# VNH2SP30.net
KiCad netlist of a schematic drawn in EAGLE
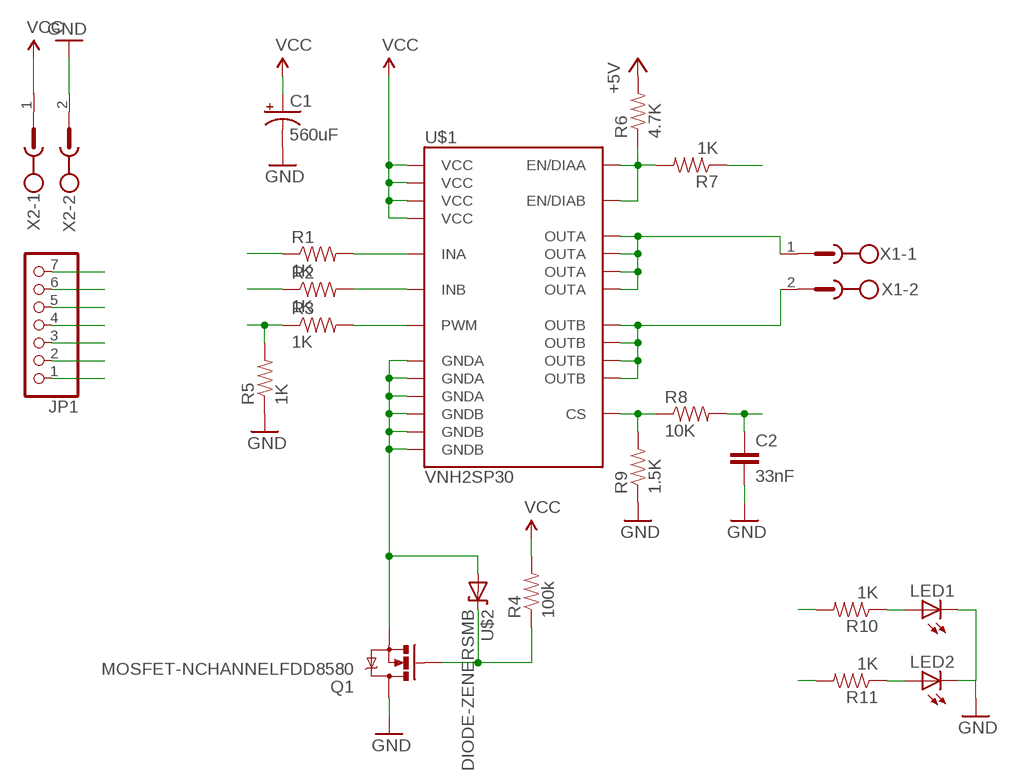
[diagram p0: schematic, sheet 1]

(export (version "E")
  (design (tool "Eeschema 10.0.6"))
  (components
    (comp (ref "C1")
      (value "560uF")
      (footprint "eagle-import:PANASONIC_G")
      (libsource (lib "eagle-import") (part "CAP_POLG"))
    )
    (comp (ref "C2")
      (value "33nF")
      (footprint "eagle-import:1206")
      (libsource (lib "eagle-import") (part "CAP1206"))
    )
    (comp (ref "JP1")
      (value "PINHD-1X7")
      (footprint "eagle-import:1X07")
      (libsource (lib "eagle-import") (part "PINHD-1X7"))
    )
    (comp (ref "LED1")
      (value "LEDCHIPLED_1206")
      (footprint "eagle-import:CHIPLED_1206")
      (libsource (lib "eagle-import") (part "LEDCHIPLED_1206"))
    )
    (comp (ref "LED2")
      (value "LEDCHIPLED_1206")
      (footprint "eagle-import:CHIPLED_1206")
      (libsource (lib "eagle-import") (part "LEDCHIPLED_1206"))
    )
    (comp (ref "Q1")
      (value "MOSFET-NCHANNELFDD8580")
      (footprint "eagle-import:DPAK")
      (libsource (lib "eagle-import") (part "MOSFET-NCHANNELFDD8580"))
    )
    (comp (ref "R1")
      (value "1K")
      (footprint "eagle-import:1206")
      (libsource (lib "eagle-import") (part "RESISTOR1206"))
    )
    (comp (ref "R2")
      (value "1K")
      (footprint "eagle-import:1206")
      (libsource (lib "eagle-import") (part "RESISTOR1206"))
    )
    (comp (ref "R3")
      (value "1K")
      (footprint "eagle-import:1206")
      (libsource (lib "eagle-import") (part "RESISTOR1206"))
    )
    (comp (ref "R4")
      (value "100k")
      (footprint "eagle-import:1206")
      (libsource (lib "eagle-import") (part "RESISTOR1206"))
    )
    (comp (ref "R5")
      (value "1K")
      (footprint "eagle-import:1206")
      (libsource (lib "eagle-import") (part "RESISTOR1206"))
    )
    (comp (ref "R6")
      (value "4.7K")
      (footprint "eagle-import:1206")
      (libsource (lib "eagle-import") (part "RESISTOR1206"))
    )
    (comp (ref "R7")
      (value "1K")
      (footprint "eagle-import:1206")
      (libsource (lib "eagle-import") (part "RESISTOR1206"))
    )
    (comp (ref "R8")
      (value "10K")
      (footprint "eagle-import:1206")
      (libsource (lib "eagle-import") (part "RESISTOR1206"))
    )
    (comp (ref "R9")
      (value "1.5K")
      (footprint "eagle-import:1206")
      (libsource (lib "eagle-import") (part "RESISTOR1206"))
    )
    (comp (ref "R10")
      (value "1K")
      (footprint "eagle-import:1206")
      (libsource (lib "eagle-import") (part "RESISTOR1206"))
    )
    (comp (ref "R11")
      (value "1K")
      (footprint "eagle-import:1206")
      (libsource (lib "eagle-import") (part "RESISTOR1206"))
    )
    (comp (ref "U$1")
      (value "VNH2SP30")
      (footprint "eagle-import:VNH2SP30")
      (libsource (lib "eagle-import") (part "VNH2SP30"))
    )
    (comp (ref "U$2")
      (value "DIODE-ZENERSMB")
      (footprint "eagle-import:SMB-DIODE")
      (libsource (lib "eagle-import") (part "DIODE-ZENERSMB"))
    )
    (comp (ref "X1")
      (value "MSTBV2")
      (footprint "eagle-import:MSTBV2")
      (libsource (lib "eagle-import") (part "MSTBV2"))
    )
    (comp (ref "X2")
      (value "MSTBV2")
      (footprint "eagle-import:MSTBV2")
      (libsource (lib "eagle-import") (part "MSTBV2"))
    )
  )
  (nets
    (net (code "1") (name "+5V") (class "Default")
      (node (ref "JP1") (pin "7") (pinfunction "7_7") (pintype "passive"))
      (node (ref "R6") (pin "2") (pinfunction "2_2") (pintype "passive"))
    )
    (net (code "2") (name "/CS") (class "Default")
      (node (ref "C2") (pin "1") (pinfunction "1_1") (pintype "passive"))
      (node (ref "JP1") (pin "2") (pinfunction "2_2") (pintype "passive"))
      (node (ref "R8") (pin "2") (pinfunction "2_2") (pintype "passive"))
    )
    (net (code "3") (name "/EN") (class "Default")
      (node (ref "JP1") (pin "6") (pinfunction "6_6") (pintype "passive"))
      (node (ref "R7") (pin "1") (pinfunction "1_1") (pintype "passive"))
    )
    (net (code "4") (name "/INA") (class "Default")
      (node (ref "JP1") (pin "5") (pinfunction "5_5") (pintype "passive"))
      (node (ref "R1") (pin "1") (pinfunction "1_1") (pintype "passive"))
    )
    (net (code "5") (name "/INB") (class "Default")
      (node (ref "JP1") (pin "4") (pinfunction "4_4") (pintype "passive"))
      (node (ref "R2") (pin "1") (pinfunction "1_1") (pintype "passive"))
    )
    (net (code "6") (name "/OUTA") (class "Default")
      (node (ref "R11") (pin "2") (pinfunction "2_2") (pintype "passive"))
      (node (ref "U$1") (pin "1") (pinfunction "OUTA_1") (pintype "bidirectional"))
      (node (ref "U$1") (pin "25") (pinfunction "OUTA_25") (pintype "bidirectional"))
      (node (ref "U$1") (pin "30") (pinfunction "OUTA_30") (pintype "bidirectional"))
      (node (ref "U$1") (pin "SLUG3") (pinfunction "OUTA_SLUG3") (pintype "bidirectional"))
      (node (ref "X1") (pin "1") (pinfunction "SK_1") (pintype "passive"))
    )
    (net (code "7") (name "/OUTB") (class "Default")
      (node (ref "R10") (pin "2") (pinfunction "2_2") (pintype "passive"))
      (node (ref "U$1") (pin "15") (pinfunction "OUTB_15") (pintype "bidirectional"))
      (node (ref "U$1") (pin "16") (pinfunction "OUTB_16") (pintype "bidirectional"))
      (node (ref "U$1") (pin "21") (pinfunction "OUTB_21") (pintype "bidirectional"))
      (node (ref "U$1") (pin "SLUG2") (pinfunction "OUTB_SLUG2") (pintype "bidirectional"))
      (node (ref "X1") (pin "2") (pinfunction "SK_2") (pintype "passive"))
    )
    (net (code "8") (name "/PWM") (class "Default")
      (node (ref "JP1") (pin "3") (pinfunction "3_3") (pintype "passive"))
      (node (ref "R3") (pin "1") (pinfunction "1_1") (pintype "passive"))
      (node (ref "R5") (pin "2") (pinfunction "2_2") (pintype "passive"))
    )
    (net (code "9") (name "GND") (class "Default")
      (node (ref "C1") (pin "-") (pinfunction "-_-") (pintype "passive"))
      (node (ref "C2") (pin "2") (pinfunction "2_2") (pintype "passive"))
      (node (ref "JP1") (pin "1") (pinfunction "1_1") (pintype "passive"))
      (node (ref "LED1") (pin "C") (pinfunction "C_C") (pintype "passive"))
      (node (ref "LED2") (pin "C") (pinfunction "C_C") (pintype "passive"))
      (node (ref "Q1") (pin "4") (pinfunction "D_4") (pintype "passive"))
      (node (ref "R5") (pin "1") (pinfunction "1_1") (pintype "passive"))
      (node (ref "R9") (pin "1") (pinfunction "1_1") (pintype "passive"))
      (node (ref "X2") (pin "2") (pinfunction "SK_2") (pintype "passive"))
    )
    (net (code "10") (name "Net-(LED1-PadA)") (class "Default")
      (node (ref "LED1") (pin "A") (pinfunction "A_A") (pintype "passive"))
      (node (ref "R10") (pin "1") (pinfunction "1_1") (pintype "passive"))
    )
    (net (code "11") (name "Net-(LED2-PadA)") (class "Default")
      (node (ref "LED2") (pin "A") (pinfunction "A_A") (pintype "passive"))
      (node (ref "R11") (pin "1") (pinfunction "1_1") (pintype "passive"))
    )
    (net (code "12") (name "Net-(Q1-G)") (class "Default")
      (node (ref "Q1") (pin "1") (pinfunction "G_1") (pintype "passive"))
      (node (ref "R4") (pin "1") (pinfunction "1_1") (pintype "passive"))
      (node (ref "U$2") (pin "C") (pinfunction "C_C") (pintype "passive"))
    )
    (net (code "13") (name "Net-(Q1-S)") (class "Default")
      (node (ref "Q1") (pin "3") (pinfunction "S_3") (pintype "passive"))
      (node (ref "U$1") (pin "18") (pinfunction "GNDB_18") (pintype "bidirectional"))
      (node (ref "U$1") (pin "19") (pinfunction "GNDB_19") (pintype "bidirectional"))
      (node (ref "U$1") (pin "20") (pinfunction "GNDB_20") (pintype "bidirectional"))
      (node (ref "U$1") (pin "26") (pinfunction "GNDA_26") (pintype "bidirectional"))
      (node (ref "U$1") (pin "27") (pinfunction "GNDA_27") (pintype "bidirectional"))
      (node (ref "U$1") (pin "28") (pinfunction "GNDA_28") (pintype "bidirectional"))
      (node (ref "U$2") (pin "A") (pinfunction "A_A") (pintype "passive"))
    )
    (net (code "14") (name "Net-(U$1-CS)") (class "Default")
      (node (ref "R8") (pin "1") (pinfunction "1_1") (pintype "passive"))
      (node (ref "R9") (pin "2") (pinfunction "2_2") (pintype "passive"))
      (node (ref "U$1") (pin "9") (pinfunction "CS_9") (pintype "bidirectional"))
    )
    (net (code "15") (name "Net-(U$1-EN{slash}DIAA)") (class "Default")
      (node (ref "R6") (pin "1") (pinfunction "1_1") (pintype "passive"))
      (node (ref "R7") (pin "2") (pinfunction "2_2") (pintype "passive"))
      (node (ref "U$1") (pin "10") (pinfunction "EN/DIAB_10") (pintype "bidirectional"))
      (node (ref "U$1") (pin "6") (pinfunction "EN/DIAA_6") (pintype "bidirectional"))
    )
    (net (code "16") (name "Net-(U$1-INA)") (class "Default")
      (node (ref "R1") (pin "2") (pinfunction "2_2") (pintype "passive"))
      (node (ref "U$1") (pin "5") (pinfunction "INA_5") (pintype "bidirectional"))
    )
    (net (code "17") (name "Net-(U$1-INB)") (class "Default")
      (node (ref "R2") (pin "2") (pinfunction "2_2") (pintype "passive"))
      (node (ref "U$1") (pin "11") (pinfunction "INB_11") (pintype "bidirectional"))
    )
    (net (code "18") (name "Net-(U$1-PWM)") (class "Default")
      (node (ref "R3") (pin "2") (pinfunction "2_2") (pintype "passive"))
      (node (ref "U$1") (pin "8") (pinfunction "PWM_8") (pintype "bidirectional"))
    )
    (net (code "19") (name "VCC") (class "Default")
      (node (ref "C1") (pin "+") (pinfunction "+_+") (pintype "passive"))
      (node (ref "R4") (pin "2") (pinfunction "2_2") (pintype "passive"))
      (node (ref "U$1") (pin "13") (pinfunction "VCC_13") (pintype "bidirectional"))
      (node (ref "U$1") (pin "23") (pinfunction "VCC_23") (pintype "bidirectional"))
      (node (ref "U$1") (pin "3") (pinfunction "VCC_3") (pintype "bidirectional"))
      (node (ref "U$1") (pin "SLUG1") (pinfunction "VCC_SLUG1") (pintype "bidirectional"))
      (node (ref "X2") (pin "1") (pinfunction "SK_1") (pintype "passive"))
    )
  )
)
